# buffer.net
KiCad netlist of a schematic drawn in Altium Designer
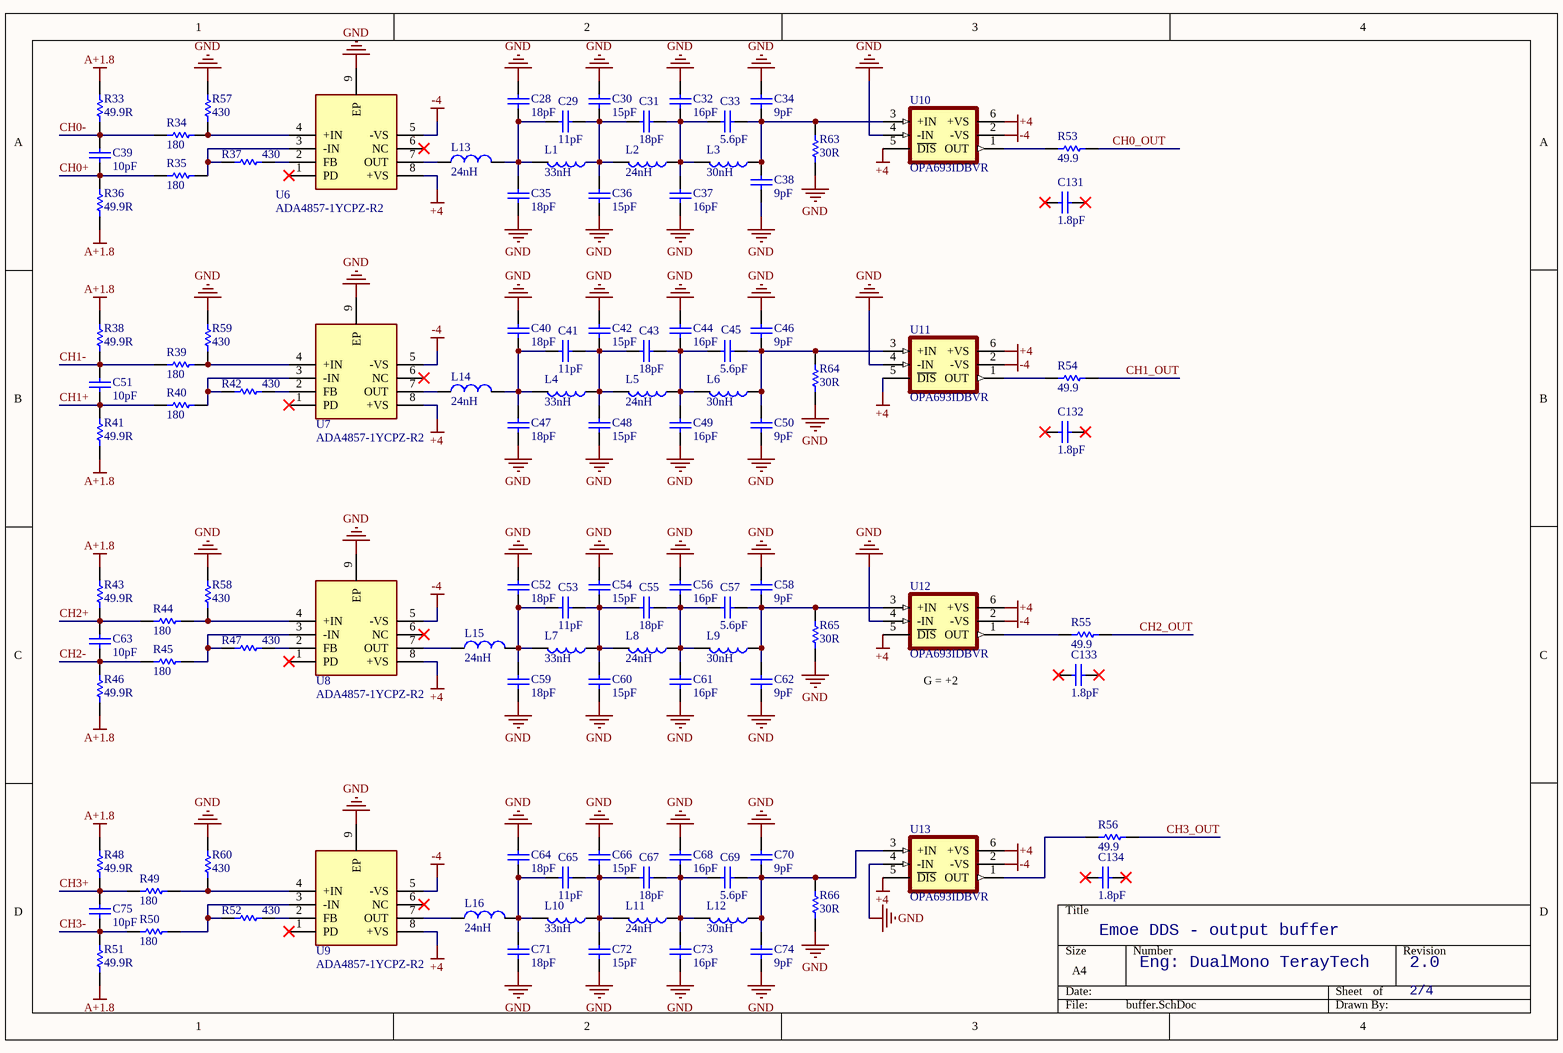
[diagram p0: buffer.SchDoc]

(export (version "E")
  (design (tool "Eeschema 10.0.6"))
  (components
    (comp (ref "C28")
      (value "18pF")
      (footprint "0402")
      (description "Capacitor")
      (fields (field (name "PUBLISHER") "Altium Limited"))
      (libsource (lib "My Footprint") (part "CAP"))
    )
    (comp (ref "C29")
      (value "11pF")
      (footprint "0402")
      (description "Capacitor")
      (fields (field (name "PUBLISHER") "Altium Limited"))
      (libsource (lib "My Footprint") (part "CAP"))
    )
    (comp (ref "C30")
      (value "15pF")
      (footprint "0402")
      (description "Capacitor")
      (fields (field (name "PUBLISHER") "Altium Limited"))
      (libsource (lib "My Footprint") (part "CAP"))
    )
    (comp (ref "C31")
      (value "18pF")
      (footprint "0402")
      (description "Capacitor")
      (fields (field (name "PUBLISHER") "Altium Limited"))
      (libsource (lib "My Footprint") (part "CAP"))
    )
    (comp (ref "C32")
      (value "16pF")
      (footprint "0402")
      (description "Capacitor")
      (fields (field (name "PUBLISHER") "Altium Limited"))
      (libsource (lib "My Footprint") (part "CAP"))
    )
    (comp (ref "C33")
      (value "5.6pF")
      (footprint "0402")
      (description "Capacitor")
      (fields (field (name "PUBLISHER") "Altium Limited"))
      (libsource (lib "My Footprint") (part "CAP"))
    )
    (comp (ref "C34")
      (value "9pF")
      (footprint "0402")
      (description "Capacitor")
      (fields (field (name "PUBLISHER") "Altium Limited"))
      (libsource (lib "My Footprint") (part "CAP"))
    )
    (comp (ref "C35")
      (value "18pF")
      (footprint "0402")
      (description "Capacitor")
      (fields (field (name "PUBLISHER") "Altium Limited"))
      (libsource (lib "My Footprint") (part "CAP"))
    )
    (comp (ref "C36")
      (value "15pF")
      (footprint "0402")
      (description "Capacitor")
      (fields (field (name "PUBLISHER") "Altium Limited"))
      (libsource (lib "My Footprint") (part "CAP"))
    )
    (comp (ref "C37")
      (value "16pF")
      (footprint "0402")
      (description "Capacitor")
      (fields (field (name "PUBLISHER") "Altium Limited"))
      (libsource (lib "My Footprint") (part "CAP"))
    )
    (comp (ref "C38")
      (value "9pF")
      (footprint "0402")
      (description "Capacitor")
      (fields (field (name "PUBLISHER") "Altium Limited"))
      (libsource (lib "My Footprint") (part "CAP"))
    )
    (comp (ref "C39")
      (value "10pF")
      (footprint "0402")
      (description "Capacitor")
      (fields (field (name "PUBLISHER") "Altium Limited"))
      (libsource (lib "My Footprint") (part "CAP"))
    )
    (comp (ref "C40")
      (value "18pF")
      (footprint "0402")
      (description "Capacitor")
      (fields (field (name "PUBLISHER") "Altium Limited"))
      (libsource (lib "My Footprint") (part "CAP"))
    )
    (comp (ref "C41")
      (value "11pF")
      (footprint "0402")
      (description "Capacitor")
      (fields (field (name "PUBLISHER") "Altium Limited"))
      (libsource (lib "My Footprint") (part "CAP"))
    )
    (comp (ref "C42")
      (value "15pF")
      (footprint "0402")
      (description "Capacitor")
      (fields (field (name "PUBLISHER") "Altium Limited"))
      (libsource (lib "My Footprint") (part "CAP"))
    )
    (comp (ref "C43")
      (value "18pF")
      (footprint "0402")
      (description "Capacitor")
      (fields (field (name "PUBLISHER") "Altium Limited"))
      (libsource (lib "My Footprint") (part "CAP"))
    )
    (comp (ref "C44")
      (value "16pF")
      (footprint "0402")
      (description "Capacitor")
      (fields (field (name "PUBLISHER") "Altium Limited"))
      (libsource (lib "My Footprint") (part "CAP"))
    )
    (comp (ref "C45")
      (value "5.6pF")
      (footprint "0402")
      (description "Capacitor")
      (fields (field (name "PUBLISHER") "Altium Limited"))
      (libsource (lib "My Footprint") (part "CAP"))
    )
    (comp (ref "C46")
      (value "9pF")
      (footprint "0402")
      (description "Capacitor")
      (fields (field (name "PUBLISHER") "Altium Limited"))
      (libsource (lib "My Footprint") (part "CAP"))
    )
    (comp (ref "C47")
      (value "18pF")
      (footprint "0402")
      (description "Capacitor")
      (fields (field (name "PUBLISHER") "Altium Limited"))
      (libsource (lib "My Footprint") (part "CAP"))
    )
    (comp (ref "C48")
      (value "15pF")
      (footprint "0402")
      (description "Capacitor")
      (fields (field (name "PUBLISHER") "Altium Limited"))
      (libsource (lib "My Footprint") (part "CAP"))
    )
    (comp (ref "C49")
      (value "16pF")
      (footprint "0402")
      (description "Capacitor")
      (fields (field (name "PUBLISHER") "Altium Limited"))
      (libsource (lib "My Footprint") (part "CAP"))
    )
    (comp (ref "C50")
      (value "9pF")
      (footprint "0402")
      (description "Capacitor")
      (fields (field (name "PUBLISHER") "Altium Limited"))
      (libsource (lib "My Footprint") (part "CAP"))
    )
    (comp (ref "C51")
      (value "10pF")
      (footprint "0402")
      (description "Capacitor")
      (fields (field (name "PUBLISHER") "Altium Limited"))
      (libsource (lib "My Footprint") (part "CAP"))
    )
    (comp (ref "C52")
      (value "18pF")
      (footprint "0402")
      (description "Capacitor")
      (fields (field (name "PUBLISHER") "Altium Limited"))
      (libsource (lib "My Footprint") (part "CAP"))
    )
    (comp (ref "C53")
      (value "11pF")
      (footprint "0402")
      (description "Capacitor")
      (fields (field (name "PUBLISHER") "Altium Limited"))
      (libsource (lib "My Footprint") (part "CAP"))
    )
    (comp (ref "C54")
      (value "15pF")
      (footprint "0402")
      (description "Capacitor")
      (fields (field (name "PUBLISHER") "Altium Limited"))
      (libsource (lib "My Footprint") (part "CAP"))
    )
    (comp (ref "C55")
      (value "18pF")
      (footprint "0402")
      (description "Capacitor")
      (fields (field (name "PUBLISHER") "Altium Limited"))
      (libsource (lib "My Footprint") (part "CAP"))
    )
    (comp (ref "C56")
      (value "16pF")
      (footprint "0402")
      (description "Capacitor")
      (fields (field (name "PUBLISHER") "Altium Limited"))
      (libsource (lib "My Footprint") (part "CAP"))
    )
    (comp (ref "C57")
      (value "5.6pF")
      (footprint "0402")
      (description "Capacitor")
      (fields (field (name "PUBLISHER") "Altium Limited"))
      (libsource (lib "My Footprint") (part "CAP"))
    )
    (comp (ref "C58")
      (value "9pF")
      (footprint "0402")
      (description "Capacitor")
      (fields (field (name "PUBLISHER") "Altium Limited"))
      (libsource (lib "My Footprint") (part "CAP"))
    )
    (comp (ref "C59")
      (value "18pF")
      (footprint "0402")
      (description "Capacitor")
      (fields (field (name "PUBLISHER") "Altium Limited"))
      (libsource (lib "My Footprint") (part "CAP"))
    )
    (comp (ref "C60")
      (value "15pF")
      (footprint "0402")
      (description "Capacitor")
      (fields (field (name "PUBLISHER") "Altium Limited"))
      (libsource (lib "My Footprint") (part "CAP"))
    )
    (comp (ref "C61")
      (value "16pF")
      (footprint "0402")
      (description "Capacitor")
      (fields (field (name "PUBLISHER") "Altium Limited"))
      (libsource (lib "My Footprint") (part "CAP"))
    )
    (comp (ref "C62")
      (value "9pF")
      (footprint "0402")
      (description "Capacitor")
      (fields (field (name "PUBLISHER") "Altium Limited"))
      (libsource (lib "My Footprint") (part "CAP"))
    )
    (comp (ref "C63")
      (value "10pF")
      (footprint "0402")
      (description "Capacitor")
      (fields (field (name "PUBLISHER") "Altium Limited"))
      (libsource (lib "My Footprint") (part "CAP"))
    )
    (comp (ref "C64")
      (value "18pF")
      (footprint "0402")
      (description "Capacitor")
      (fields (field (name "PUBLISHER") "Altium Limited"))
      (libsource (lib "My Footprint") (part "CAP"))
    )
    (comp (ref "C65")
      (value "11pF")
      (footprint "0402")
      (description "Capacitor")
      (fields (field (name "PUBLISHER") "Altium Limited"))
      (libsource (lib "My Footprint") (part "CAP"))
    )
    (comp (ref "C66")
      (value "15pF")
      (footprint "0402")
      (description "Capacitor")
      (fields (field (name "PUBLISHER") "Altium Limited"))
      (libsource (lib "My Footprint") (part "CAP"))
    )
    (comp (ref "C67")
      (value "18pF")
      (footprint "0402")
      (description "Capacitor")
      (fields (field (name "PUBLISHER") "Altium Limited"))
      (libsource (lib "My Footprint") (part "CAP"))
    )
    (comp (ref "C68")
      (value "16pF")
      (footprint "0402")
      (description "Capacitor")
      (fields (field (name "PUBLISHER") "Altium Limited"))
      (libsource (lib "My Footprint") (part "CAP"))
    )
    (comp (ref "C69")
      (value "5.6pF")
      (footprint "0402")
      (description "Capacitor")
      (fields (field (name "PUBLISHER") "Altium Limited"))
      (libsource (lib "My Footprint") (part "CAP"))
    )
    (comp (ref "C70")
      (value "9pF")
      (footprint "0402")
      (description "Capacitor")
      (fields (field (name "PUBLISHER") "Altium Limited"))
      (libsource (lib "My Footprint") (part "CAP"))
    )
    (comp (ref "C71")
      (value "18pF")
      (footprint "0402")
      (description "Capacitor")
      (fields (field (name "PUBLISHER") "Altium Limited"))
      (libsource (lib "My Footprint") (part "CAP"))
    )
    (comp (ref "C72")
      (value "15pF")
      (footprint "0402")
      (description "Capacitor")
      (fields (field (name "PUBLISHER") "Altium Limited"))
      (libsource (lib "My Footprint") (part "CAP"))
    )
    (comp (ref "C73")
      (value "16pF")
      (footprint "0402")
      (description "Capacitor")
      (fields (field (name "PUBLISHER") "Altium Limited"))
      (libsource (lib "My Footprint") (part "CAP"))
    )
    (comp (ref "C74")
      (value "9pF")
      (footprint "0402")
      (description "Capacitor")
      (fields (field (name "PUBLISHER") "Altium Limited"))
      (libsource (lib "My Footprint") (part "CAP"))
    )
    (comp (ref "C75")
      (value "10pF")
      (footprint "0402")
      (description "Capacitor")
      (fields (field (name "PUBLISHER") "Altium Limited"))
      (libsource (lib "My Footprint") (part "CAP"))
    )
    (comp (ref "C131")
      (value "1.8pF")
      (footprint "0402")
      (description "Capacitor")
      (fields (field (name "PUBLISHER") "Altium Limited"))
      (libsource (lib "My Footprint") (part "CAP"))
    )
    (comp (ref "C132")
      (value "1.8pF")
      (footprint "0402")
      (description "Capacitor")
      (fields (field (name "PUBLISHER") "Altium Limited"))
      (libsource (lib "My Footprint") (part "CAP"))
    )
    (comp (ref "C133")
      (value "1.8pF")
      (footprint "0402")
      (description "Capacitor")
      (fields (field (name "PUBLISHER") "Altium Limited"))
      (libsource (lib "My Footprint") (part "CAP"))
    )
    (comp (ref "C134")
      (value "1.8pF")
      (footprint "0402")
      (description "Capacitor")
      (fields (field (name "PUBLISHER") "Altium Limited"))
      (libsource (lib "My Footprint") (part "CAP"))
    )
    (comp (ref "L1") (value "33nH") (footprint "0402") (libsource (lib "My Footprint") (part "FB")))
    (comp (ref "L2") (value "24nH") (footprint "0402") (libsource (lib "My Footprint") (part "FB")))
    (comp (ref "L3") (value "30nH") (footprint "0402") (libsource (lib "My Footprint") (part "FB")))
    (comp (ref "L4") (value "33nH") (footprint "0402") (libsource (lib "My Footprint") (part "FB")))
    (comp (ref "L5") (value "24nH") (footprint "0402") (libsource (lib "My Footprint") (part "FB")))
    (comp (ref "L6") (value "30nH") (footprint "0402") (libsource (lib "My Footprint") (part "FB")))
    (comp (ref "L7") (value "33nH") (footprint "0402") (libsource (lib "My Footprint") (part "FB")))
    (comp (ref "L8") (value "24nH") (footprint "0402") (libsource (lib "My Footprint") (part "FB")))
    (comp (ref "L9") (value "30nH") (footprint "0402") (libsource (lib "My Footprint") (part "FB")))
    (comp (ref "L10") (value "33nH") (footprint "0402") (libsource (lib "My Footprint") (part "FB")))
    (comp (ref "L11") (value "24nH") (footprint "0402") (libsource (lib "My Footprint") (part "FB")))
    (comp (ref "L12") (value "30nH") (footprint "0402") (libsource (lib "My Footprint") (part "FB")))
    (comp (ref "L13") (value "24nH") (footprint "0402L") (libsource (lib "My Footprint") (part "Inductor")))
    (comp (ref "L14") (value "24nH") (footprint "0402L") (libsource (lib "My Footprint") (part "Inductor")))
    (comp (ref "L15") (value "24nH") (footprint "0402L") (libsource (lib "My Footprint") (part "Inductor")))
    (comp (ref "L16") (value "24nH") (footprint "0402L") (libsource (lib "My Footprint") (part "Inductor")))
    (comp (ref "R33")
      (value "49.9R")
      (footprint "0402")
      (description "Resistor")
      (fields (field (name "PUBLISHER") "Altium Limited"))
      (libsource (lib "My Footprint") (part "RES"))
    )
    (comp (ref "R34")
      (value "180")
      (footprint "0402")
      (description "Resistor")
      (fields (field (name "PUBLISHER") "Altium Limited"))
      (libsource (lib "My Footprint") (part "RES"))
    )
    (comp (ref "R35")
      (value "180")
      (footprint "0402")
      (description "Resistor")
      (fields (field (name "PUBLISHER") "Altium Limited"))
      (libsource (lib "My Footprint") (part "RES"))
    )
    (comp (ref "R36")
      (value "49.9R")
      (footprint "0402")
      (description "Resistor")
      (fields (field (name "PUBLISHER") "Altium Limited"))
      (libsource (lib "My Footprint") (part "RES"))
    )
    (comp (ref "R37")
      (value "430")
      (footprint "0402")
      (description "Resistor")
      (fields (field (name "PUBLISHER") "Altium Limited"))
      (libsource (lib "My Footprint") (part "RES"))
    )
    (comp (ref "R38")
      (value "49.9R")
      (footprint "0402")
      (description "Resistor")
      (fields (field (name "PUBLISHER") "Altium Limited"))
      (libsource (lib "My Footprint") (part "RES"))
    )
    (comp (ref "R39")
      (value "180")
      (footprint "0402")
      (description "Resistor")
      (fields (field (name "PUBLISHER") "Altium Limited"))
      (libsource (lib "My Footprint") (part "RES"))
    )
    (comp (ref "R40")
      (value "180")
      (footprint "0402")
      (description "Resistor")
      (fields (field (name "PUBLISHER") "Altium Limited"))
      (libsource (lib "My Footprint") (part "RES"))
    )
    (comp (ref "R41")
      (value "49.9R")
      (footprint "0402")
      (description "Resistor")
      (fields (field (name "PUBLISHER") "Altium Limited"))
      (libsource (lib "My Footprint") (part "RES"))
    )
    (comp (ref "R42")
      (value "430")
      (footprint "0402")
      (description "Resistor")
      (fields (field (name "PUBLISHER") "Altium Limited"))
      (libsource (lib "My Footprint") (part "RES"))
    )
    (comp (ref "R43")
      (value "49.9R")
      (footprint "0402")
      (description "Resistor")
      (fields (field (name "PUBLISHER") "Altium Limited"))
      (libsource (lib "My Footprint") (part "RES"))
    )
    (comp (ref "R44")
      (value "180")
      (footprint "0402")
      (description "Resistor")
      (fields (field (name "PUBLISHER") "Altium Limited"))
      (libsource (lib "My Footprint") (part "RES"))
    )
    (comp (ref "R45")
      (value "180")
      (footprint "0402")
      (description "Resistor")
      (fields (field (name "PUBLISHER") "Altium Limited"))
      (libsource (lib "My Footprint") (part "RES"))
    )
    (comp (ref "R46")
      (value "49.9R")
      (footprint "0402")
      (description "Resistor")
      (fields (field (name "PUBLISHER") "Altium Limited"))
      (libsource (lib "My Footprint") (part "RES"))
    )
    (comp (ref "R47")
      (value "430")
      (footprint "0402")
      (description "Resistor")
      (fields (field (name "PUBLISHER") "Altium Limited"))
      (libsource (lib "My Footprint") (part "RES"))
    )
    (comp (ref "R48")
      (value "49.9R")
      (footprint "0402")
      (description "Resistor")
      (fields (field (name "PUBLISHER") "Altium Limited"))
      (libsource (lib "My Footprint") (part "RES"))
    )
    (comp (ref "R49")
      (value "180")
      (footprint "0402")
      (description "Resistor")
      (fields (field (name "PUBLISHER") "Altium Limited"))
      (libsource (lib "My Footprint") (part "RES"))
    )
    (comp (ref "R50")
      (value "180")
      (footprint "0402")
      (description "Resistor")
      (fields (field (name "PUBLISHER") "Altium Limited"))
      (libsource (lib "My Footprint") (part "RES"))
    )
    (comp (ref "R51")
      (value "49.9R")
      (footprint "0402")
      (description "Resistor")
      (fields (field (name "PUBLISHER") "Altium Limited"))
      (libsource (lib "My Footprint") (part "RES"))
    )
    (comp (ref "R52")
      (value "430")
      (footprint "0402")
      (description "Resistor")
      (fields (field (name "PUBLISHER") "Altium Limited"))
      (libsource (lib "My Footprint") (part "RES"))
    )
    (comp (ref "R53")
      (value "49.9")
      (footprint "0603")
      (description "Resistor")
      (fields (field (name "PUBLISHER") "Altium Limited"))
      (libsource (lib "My Footprint") (part "RES"))
    )
    (comp (ref "R54")
      (value "49.9")
      (footprint "0603")
      (description "Resistor")
      (fields (field (name "PUBLISHER") "Altium Limited"))
      (libsource (lib "My Footprint") (part "RES"))
    )
    (comp (ref "R55")
      (value "49.9")
      (footprint "0603")
      (description "Resistor")
      (fields (field (name "PUBLISHER") "Altium Limited"))
      (libsource (lib "My Footprint") (part "RES"))
    )
    (comp (ref "R56")
      (value "49.9")
      (footprint "0603")
      (description "Resistor")
      (fields (field (name "PUBLISHER") "Altium Limited"))
      (libsource (lib "My Footprint") (part "RES"))
    )
    (comp (ref "R57")
      (value "430")
      (footprint "0402")
      (description "Resistor")
      (fields (field (name "PUBLISHER") "Altium Limited"))
      (libsource (lib "My Footprint") (part "RES"))
    )
    (comp (ref "R58")
      (value "430")
      (footprint "0402")
      (description "Resistor")
      (fields (field (name "PUBLISHER") "Altium Limited"))
      (libsource (lib "My Footprint") (part "RES"))
    )
    (comp (ref "R59")
      (value "430")
      (footprint "0402")
      (description "Resistor")
      (fields (field (name "PUBLISHER") "Altium Limited"))
      (libsource (lib "My Footprint") (part "RES"))
    )
    (comp (ref "R60")
      (value "430")
      (footprint "0402")
      (description "Resistor")
      (fields (field (name "PUBLISHER") "Altium Limited"))
      (libsource (lib "My Footprint") (part "RES"))
    )
    (comp (ref "R63")
      (value "30R")
      (footprint "0402L")
      (description "Resistor")
      (fields (field (name "PUBLISHER") "Altium Limited"))
      (libsource (lib "My Footprint") (part "RES"))
    )
    (comp (ref "R64")
      (value "30R")
      (footprint "0402L")
      (description "Resistor")
      (fields (field (name "PUBLISHER") "Altium Limited"))
      (libsource (lib "My Footprint") (part "RES"))
    )
    (comp (ref "R65")
      (value "30R")
      (footprint "0402L")
      (description "Resistor")
      (fields (field (name "PUBLISHER") "Altium Limited"))
      (libsource (lib "My Footprint") (part "RES"))
    )
    (comp (ref "R66")
      (value "30R")
      (footprint "0402L")
      (description "Resistor")
      (fields (field (name "PUBLISHER") "Altium Limited"))
      (libsource (lib "My Footprint") (part "RES"))
    )
    (comp (ref "U6")
      (value "ADA4857-1YCPZ-R2")
      (footprint "SamacSys:SON50P300X300X85-9N-D")
      (description "Integrated Circuit")
      (fields (field (name "MOUSER PART NUMBER") "584-ADA4857-1YCPZ-R2"))
      (libsource (lib "SamacSys") (part "ADA4857-1YCPZ-R2"))
    )
    (comp (ref "U7")
      (value "ADA4857-1YCPZ-R2")
      (footprint "SamacSys:SON50P300X300X85-9N-D")
      (description "Integrated Circuit")
      (fields (field (name "MOUSER PART NUMBER") "584-ADA4857-1YCPZ-R2"))
      (libsource (lib "SamacSys") (part "ADA4857-1YCPZ-R2"))
    )
    (comp (ref "U8")
      (value "ADA4857-1YCPZ-R2")
      (footprint "SamacSys:SON50P300X300X85-9N-D")
      (description "Integrated Circuit")
      (fields (field (name "MOUSER PART NUMBER") "584-ADA4857-1YCPZ-R2"))
      (libsource (lib "SamacSys") (part "ADA4857-1YCPZ-R2"))
    )
    (comp (ref "U9")
      (value "ADA4857-1YCPZ-R2")
      (footprint "SamacSys:SON50P300X300X85-9N-D")
      (description "Integrated Circuit")
      (fields (field (name "MOUSER PART NUMBER") "584-ADA4857-1YCPZ-R2"))
      (libsource (lib "SamacSys") (part "ADA4857-1YCPZ-R2"))
    )
    (comp (ref "U10")
      (value "OPA693IDBVR")
      (footprint "SOT95P280X145-6N")
      (description "Ultra-Wideband, Fixed Gain Video Buffer Amplifier with Disable")
      (fields (field (name "MF") "Texas Instruments"))
      (libsource (lib "OPA693") (part "OPA693IDBVR"))
    )
    (comp (ref "U11")
      (value "OPA693IDBVR")
      (footprint "SOT95P280X145-6N")
      (description "Ultra-Wideband, Fixed Gain Video Buffer Amplifier with Disable")
      (fields (field (name "MF") "Texas Instruments"))
      (libsource (lib "OPA693") (part "OPA693IDBVR"))
    )
    (comp (ref "U12")
      (value "OPA693IDBVR")
      (footprint "SOT95P280X145-6N")
      (description "Ultra-Wideband, Fixed Gain Video Buffer Amplifier with Disable")
      (fields (field (name "MF") "Texas Instruments"))
      (libsource (lib "OPA693") (part "OPA693IDBVR"))
    )
    (comp (ref "U13")
      (value "OPA693IDBVR")
      (footprint "SOT95P280X145-6N")
      (description "Ultra-Wideband, Fixed Gain Video Buffer Amplifier with Disable")
      (fields (field (name "MF") "Texas Instruments"))
      (libsource (lib "OPA693") (part "OPA693IDBVR"))
    )
  )
  (nets
    (net (code "1") (name "+4") (class "Default")
      (node (ref "U10") (pin "5") (pinfunction "~{DIS}_5") (pintype "passive"))
      (node (ref "U10") (pin "6") (pinfunction "+VS_6") (pintype "power_in"))
      (node (ref "U11") (pin "5") (pinfunction "~{DIS}_5") (pintype "passive"))
      (node (ref "U11") (pin "6") (pinfunction "+VS_6") (pintype "power_in"))
      (node (ref "U12") (pin "5") (pinfunction "~{DIS}_5") (pintype "passive"))
      (node (ref "U12") (pin "6") (pinfunction "+VS_6") (pintype "power_in"))
      (node (ref "U13") (pin "5") (pinfunction "~{DIS}_5") (pintype "passive"))
      (node (ref "U13") (pin "6") (pinfunction "+VS_6") (pintype "power_in"))
      (node (ref "U6") (pin "8") (pinfunction "+VS_8") (pintype "passive"))
      (node (ref "U7") (pin "8") (pinfunction "+VS_8") (pintype "passive"))
      (node (ref "U8") (pin "8") (pinfunction "+VS_8") (pintype "passive"))
      (node (ref "U9") (pin "8") (pinfunction "+VS_8") (pintype "passive"))
    )
    (net (code "2") (name "-4") (class "Default")
      (node (ref "U10") (pin "2") (pinfunction "-VS_2") (pintype "power_in"))
      (node (ref "U11") (pin "2") (pinfunction "-VS_2") (pintype "power_in"))
      (node (ref "U12") (pin "2") (pinfunction "-VS_2") (pintype "power_in"))
      (node (ref "U13") (pin "2") (pinfunction "-VS_2") (pintype "power_in"))
      (node (ref "U6") (pin "5") (pinfunction "-VS_5") (pintype "passive"))
      (node (ref "U7") (pin "5") (pinfunction "-VS_5") (pintype "passive"))
      (node (ref "U8") (pin "5") (pinfunction "-VS_5") (pintype "passive"))
      (node (ref "U9") (pin "5") (pinfunction "-VS_5") (pintype "passive"))
    )
    (net (code "3") (name "/CH0+") (class "Default")
      (node (ref "C39") (pin "1") (pinfunction "1_1") (pintype "passive"))
      (node (ref "R35") (pin "1") (pinfunction "1_1") (pintype "passive"))
      (node (ref "R36") (pin "1") (pinfunction "1_1") (pintype "passive"))
    )
    (net (code "4") (name "/CH0-") (class "Default")
      (node (ref "C39") (pin "2") (pinfunction "2_2") (pintype "passive"))
      (node (ref "R33") (pin "2") (pinfunction "2_2") (pintype "passive"))
      (node (ref "R34") (pin "1") (pinfunction "1_1") (pintype "passive"))
    )
    (net (code "5") (name "/CH0_OUT") (class "Default")
      (node (ref "R53") (pin "2") (pinfunction "2_2") (pintype "passive"))
    )
    (net (code "6") (name "/CH1+") (class "Default")
      (node (ref "C51") (pin "1") (pinfunction "1_1") (pintype "passive"))
      (node (ref "R40") (pin "1") (pinfunction "1_1") (pintype "passive"))
      (node (ref "R41") (pin "1") (pinfunction "1_1") (pintype "passive"))
    )
    (net (code "7") (name "/CH1-") (class "Default")
      (node (ref "C51") (pin "2") (pinfunction "2_2") (pintype "passive"))
      (node (ref "R38") (pin "2") (pinfunction "2_2") (pintype "passive"))
      (node (ref "R39") (pin "1") (pinfunction "1_1") (pintype "passive"))
    )
    (net (code "8") (name "/CH1_OUT") (class "Default")
      (node (ref "R54") (pin "2") (pinfunction "2_2") (pintype "passive"))
    )
    (net (code "9") (name "/CH2+") (class "Default")
      (node (ref "C63") (pin "2") (pinfunction "2_2") (pintype "passive"))
      (node (ref "R43") (pin "2") (pinfunction "2_2") (pintype "passive"))
      (node (ref "R44") (pin "1") (pinfunction "1_1") (pintype "passive"))
    )
    (net (code "10") (name "/CH2-") (class "Default")
      (node (ref "C63") (pin "1") (pinfunction "1_1") (pintype "passive"))
      (node (ref "R45") (pin "1") (pinfunction "1_1") (pintype "passive"))
      (node (ref "R46") (pin "1") (pinfunction "1_1") (pintype "passive"))
    )
    (net (code "11") (name "/CH2_OUT") (class "Default")
      (node (ref "R55") (pin "2") (pinfunction "2_2") (pintype "passive"))
    )
    (net (code "12") (name "/CH3+") (class "Default")
      (node (ref "C75") (pin "2") (pinfunction "2_2") (pintype "passive"))
      (node (ref "R48") (pin "2") (pinfunction "2_2") (pintype "passive"))
      (node (ref "R49") (pin "1") (pinfunction "1_1") (pintype "passive"))
    )
    (net (code "13") (name "/CH3-") (class "Default")
      (node (ref "C75") (pin "1") (pinfunction "1_1") (pintype "passive"))
      (node (ref "R50") (pin "1") (pinfunction "1_1") (pintype "passive"))
      (node (ref "R51") (pin "1") (pinfunction "1_1") (pintype "passive"))
    )
    (net (code "14") (name "/CH3_OUT") (class "Default")
      (node (ref "R56") (pin "2") (pinfunction "2_2") (pintype "passive"))
    )
    (net (code "15") (name "A+1.8") (class "Default")
      (node (ref "R33") (pin "1") (pinfunction "1_1") (pintype "passive"))
      (node (ref "R36") (pin "2") (pinfunction "2_2") (pintype "passive"))
      (node (ref "R38") (pin "1") (pinfunction "1_1") (pintype "passive"))
      (node (ref "R41") (pin "2") (pinfunction "2_2") (pintype "passive"))
      (node (ref "R43") (pin "1") (pinfunction "1_1") (pintype "passive"))
      (node (ref "R46") (pin "2") (pinfunction "2_2") (pintype "passive"))
      (node (ref "R48") (pin "1") (pinfunction "1_1") (pintype "passive"))
      (node (ref "R51") (pin "2") (pinfunction "2_2") (pintype "passive"))
    )
    (net (code "16") (name "GND") (class "Default")
      (node (ref "C28") (pin "1") (pinfunction "1_1") (pintype "passive"))
      (node (ref "C30") (pin "1") (pinfunction "1_1") (pintype "passive"))
      (node (ref "C32") (pin "1") (pinfunction "1_1") (pintype "passive"))
      (node (ref "C34") (pin "2") (pinfunction "2_2") (pintype "passive"))
      (node (ref "C35") (pin "2") (pinfunction "2_2") (pintype "passive"))
      (node (ref "C36") (pin "2") (pinfunction "2_2") (pintype "passive"))
      (node (ref "C37") (pin "2") (pinfunction "2_2") (pintype "passive"))
      (node (ref "C38") (pin "1") (pinfunction "1_1") (pintype "passive"))
      (node (ref "C40") (pin "1") (pinfunction "1_1") (pintype "passive"))
      (node (ref "C42") (pin "1") (pinfunction "1_1") (pintype "passive"))
      (node (ref "C44") (pin "1") (pinfunction "1_1") (pintype "passive"))
      (node (ref "C46") (pin "2") (pinfunction "2_2") (pintype "passive"))
      (node (ref "C47") (pin "2") (pinfunction "2_2") (pintype "passive"))
      (node (ref "C48") (pin "2") (pinfunction "2_2") (pintype "passive"))
      (node (ref "C49") (pin "2") (pinfunction "2_2") (pintype "passive"))
      (node (ref "C50") (pin "1") (pinfunction "1_1") (pintype "passive"))
      (node (ref "C52") (pin "1") (pinfunction "1_1") (pintype "passive"))
      (node (ref "C54") (pin "1") (pinfunction "1_1") (pintype "passive"))
      (node (ref "C56") (pin "1") (pinfunction "1_1") (pintype "passive"))
      (node (ref "C58") (pin "2") (pinfunction "2_2") (pintype "passive"))
      (node (ref "C59") (pin "2") (pinfunction "2_2") (pintype "passive"))
      (node (ref "C60") (pin "2") (pinfunction "2_2") (pintype "passive"))
      (node (ref "C61") (pin "2") (pinfunction "2_2") (pintype "passive"))
      (node (ref "C62") (pin "1") (pinfunction "1_1") (pintype "passive"))
      (node (ref "C64") (pin "1") (pinfunction "1_1") (pintype "passive"))
      (node (ref "C66") (pin "1") (pinfunction "1_1") (pintype "passive"))
      (node (ref "C68") (pin "1") (pinfunction "1_1") (pintype "passive"))
      (node (ref "C70") (pin "2") (pinfunction "2_2") (pintype "passive"))
      (node (ref "C71") (pin "2") (pinfunction "2_2") (pintype "passive"))
      (node (ref "C72") (pin "2") (pinfunction "2_2") (pintype "passive"))
      (node (ref "C73") (pin "2") (pinfunction "2_2") (pintype "passive"))
      (node (ref "C74") (pin "1") (pinfunction "1_1") (pintype "passive"))
      (node (ref "R57") (pin "2") (pinfunction "2_2") (pintype "passive"))
      (node (ref "R58") (pin "2") (pinfunction "2_2") (pintype "passive"))
      (node (ref "R59") (pin "2") (pinfunction "2_2") (pintype "passive"))
      (node (ref "R60") (pin "2") (pinfunction "2_2") (pintype "passive"))
      (node (ref "R63") (pin "1") (pinfunction "1_1") (pintype "passive"))
      (node (ref "R64") (pin "1") (pinfunction "1_1") (pintype "passive"))
      (node (ref "R65") (pin "1") (pinfunction "1_1") (pintype "passive"))
      (node (ref "R66") (pin "1") (pinfunction "1_1") (pintype "passive"))
      (node (ref "U10") (pin "4") (pinfunction "-IN_4") (pintype "input"))
      (node (ref "U11") (pin "4") (pinfunction "-IN_4") (pintype "input"))
      (node (ref "U12") (pin "4") (pinfunction "-IN_4") (pintype "input"))
      (node (ref "U13") (pin "4") (pinfunction "-IN_4") (pintype "input"))
      (node (ref "U6") (pin "9") (pinfunction "EP_9") (pintype "passive"))
      (node (ref "U7") (pin "9") (pinfunction "EP_9") (pintype "passive"))
      (node (ref "U8") (pin "9") (pinfunction "EP_9") (pintype "passive"))
      (node (ref "U9") (pin "9") (pinfunction "EP_9") (pintype "passive"))
    )
    (net (code "17") (name "Net-(C28-Pad2)") (class "Default")
      (node (ref "C28") (pin "2") (pinfunction "2_2") (pintype "passive"))
      (node (ref "C29") (pin "1") (pinfunction "1_1") (pintype "passive"))
      (node (ref "C35") (pin "1") (pinfunction "1_1") (pintype "passive"))
      (node (ref "L1") (pin "2") (pinfunction "2_2") (pintype "passive"))
      (node (ref "L13") (pin "2") (pinfunction "2_2") (pintype "passive"))
    )
    (net (code "18") (name "Net-(C29-Pad2)") (class "Default")
      (node (ref "C29") (pin "2") (pinfunction "2_2") (pintype "passive"))
      (node (ref "C30") (pin "2") (pinfunction "2_2") (pintype "passive"))
      (node (ref "C31") (pin "1") (pinfunction "1_1") (pintype "passive"))
      (node (ref "C36") (pin "1") (pinfunction "1_1") (pintype "passive"))
      (node (ref "L1") (pin "1") (pinfunction "1_1") (pintype "passive"))
      (node (ref "L2") (pin "2") (pinfunction "2_2") (pintype "passive"))
    )
    (net (code "19") (name "Net-(C31-Pad2)") (class "Default")
      (node (ref "C31") (pin "2") (pinfunction "2_2") (pintype "passive"))
      (node (ref "C32") (pin "2") (pinfunction "2_2") (pintype "passive"))
      (node (ref "C33") (pin "1") (pinfunction "1_1") (pintype "passive"))
      (node (ref "C37") (pin "1") (pinfunction "1_1") (pintype "passive"))
      (node (ref "L2") (pin "1") (pinfunction "1_1") (pintype "passive"))
      (node (ref "L3") (pin "2") (pinfunction "2_2") (pintype "passive"))
    )
    (net (code "20") (name "Net-(C40-Pad2)") (class "Default")
      (node (ref "C40") (pin "2") (pinfunction "2_2") (pintype "passive"))
      (node (ref "C41") (pin "1") (pinfunction "1_1") (pintype "passive"))
      (node (ref "C47") (pin "1") (pinfunction "1_1") (pintype "passive"))
      (node (ref "L14") (pin "2") (pinfunction "2_2") (pintype "passive"))
      (node (ref "L4") (pin "2") (pinfunction "2_2") (pintype "passive"))
    )
    (net (code "21") (name "Net-(C41-Pad2)") (class "Default")
      (node (ref "C41") (pin "2") (pinfunction "2_2") (pintype "passive"))
      (node (ref "C42") (pin "2") (pinfunction "2_2") (pintype "passive"))
      (node (ref "C43") (pin "1") (pinfunction "1_1") (pintype "passive"))
      (node (ref "C48") (pin "1") (pinfunction "1_1") (pintype "passive"))
      (node (ref "L4") (pin "1") (pinfunction "1_1") (pintype "passive"))
      (node (ref "L5") (pin "2") (pinfunction "2_2") (pintype "passive"))
    )
    (net (code "22") (name "Net-(C43-Pad2)") (class "Default")
      (node (ref "C43") (pin "2") (pinfunction "2_2") (pintype "passive"))
      (node (ref "C44") (pin "2") (pinfunction "2_2") (pintype "passive"))
      (node (ref "C45") (pin "1") (pinfunction "1_1") (pintype "passive"))
      (node (ref "C49") (pin "1") (pinfunction "1_1") (pintype "passive"))
      (node (ref "L5") (pin "1") (pinfunction "1_1") (pintype "passive"))
      (node (ref "L6") (pin "2") (pinfunction "2_2") (pintype "passive"))
    )
    (net (code "23") (name "Net-(C52-Pad2)") (class "Default")
      (node (ref "C52") (pin "2") (pinfunction "2_2") (pintype "passive"))
      (node (ref "C53") (pin "1") (pinfunction "1_1") (pintype "passive"))
      (node (ref "C59") (pin "1") (pinfunction "1_1") (pintype "passive"))
      (node (ref "L15") (pin "2") (pinfunction "2_2") (pintype "passive"))
      (node (ref "L7") (pin "2") (pinfunction "2_2") (pintype "passive"))
    )
    (net (code "24") (name "Net-(C53-Pad2)") (class "Default")
      (node (ref "C53") (pin "2") (pinfunction "2_2") (pintype "passive"))
      (node (ref "C54") (pin "2") (pinfunction "2_2") (pintype "passive"))
      (node (ref "C55") (pin "1") (pinfunction "1_1") (pintype "passive"))
      (node (ref "C60") (pin "1") (pinfunction "1_1") (pintype "passive"))
      (node (ref "L7") (pin "1") (pinfunction "1_1") (pintype "passive"))
      (node (ref "L8") (pin "2") (pinfunction "2_2") (pintype "passive"))
    )
    (net (code "25") (name "Net-(C55-Pad2)") (class "Default")
      (node (ref "C55") (pin "2") (pinfunction "2_2") (pintype "passive"))
      (node (ref "C56") (pin "2") (pinfunction "2_2") (pintype "passive"))
      (node (ref "C57") (pin "1") (pinfunction "1_1") (pintype "passive"))
      (node (ref "C61") (pin "1") (pinfunction "1_1") (pintype "passive"))
      (node (ref "L8") (pin "1") (pinfunction "1_1") (pintype "passive"))
      (node (ref "L9") (pin "2") (pinfunction "2_2") (pintype "passive"))
    )
    (net (code "26") (name "Net-(C64-Pad2)") (class "Default")
      (node (ref "C64") (pin "2") (pinfunction "2_2") (pintype "passive"))
      (node (ref "C65") (pin "1") (pinfunction "1_1") (pintype "passive"))
      (node (ref "C71") (pin "1") (pinfunction "1_1") (pintype "passive"))
      (node (ref "L10") (pin "2") (pinfunction "2_2") (pintype "passive"))
      (node (ref "L16") (pin "2") (pinfunction "2_2") (pintype "passive"))
    )
    (net (code "27") (name "Net-(C65-Pad2)") (class "Default")
      (node (ref "C65") (pin "2") (pinfunction "2_2") (pintype "passive"))
      (node (ref "C66") (pin "2") (pinfunction "2_2") (pintype "passive"))
      (node (ref "C67") (pin "1") (pinfunction "1_1") (pintype "passive"))
      (node (ref "C72") (pin "1") (pinfunction "1_1") (pintype "passive"))
      (node (ref "L10") (pin "1") (pinfunction "1_1") (pintype "passive"))
      (node (ref "L11") (pin "2") (pinfunction "2_2") (pintype "passive"))
    )
    (net (code "28") (name "Net-(C67-Pad2)") (class "Default")
      (node (ref "C67") (pin "2") (pinfunction "2_2") (pintype "passive"))
      (node (ref "C68") (pin "2") (pinfunction "2_2") (pintype "passive"))
      (node (ref "C69") (pin "1") (pinfunction "1_1") (pintype "passive"))
      (node (ref "C73") (pin "1") (pinfunction "1_1") (pintype "passive"))
      (node (ref "L11") (pin "1") (pinfunction "1_1") (pintype "passive"))
      (node (ref "L12") (pin "2") (pinfunction "2_2") (pintype "passive"))
    )
    (net (code "29") (name "Net-(U6-+IN)") (class "Default")
      (node (ref "R34") (pin "2") (pinfunction "2_2") (pintype "passive"))
      (node (ref "R57") (pin "1") (pinfunction "1_1") (pintype "passive"))
      (node (ref "U6") (pin "4") (pinfunction "+IN_4") (pintype "passive"))
    )
    (net (code "30") (name "Net-(U6--IN)") (class "Default")
      (node (ref "R35") (pin "2") (pinfunction "2_2") (pintype "passive"))
      (node (ref "R37") (pin "1") (pinfunction "1_1") (pintype "passive"))
      (node (ref "U6") (pin "3") (pinfunction "-IN_3") (pintype "passive"))
    )
    (net (code "31") (name "Net-(U6-FB)") (class "Default")
      (node (ref "R37") (pin "2") (pinfunction "2_2") (pintype "passive"))
      (node (ref "U6") (pin "2") (pinfunction "FB_2") (pintype "passive"))
    )
    (net (code "32") (name "Net-(U6-OUT)") (class "Default")
      (node (ref "L13") (pin "1") (pinfunction "1_1") (pintype "passive"))
      (node (ref "U6") (pin "7") (pinfunction "OUT_7") (pintype "passive"))
    )
    (net (code "33") (name "Net-(U7-+IN)") (class "Default")
      (node (ref "R39") (pin "2") (pinfunction "2_2") (pintype "passive"))
      (node (ref "R59") (pin "1") (pinfunction "1_1") (pintype "passive"))
      (node (ref "U7") (pin "4") (pinfunction "+IN_4") (pintype "passive"))
    )
    (net (code "34") (name "Net-(U7--IN)") (class "Default")
      (node (ref "R40") (pin "2") (pinfunction "2_2") (pintype "passive"))
      (node (ref "R42") (pin "1") (pinfunction "1_1") (pintype "passive"))
      (node (ref "U7") (pin "3") (pinfunction "-IN_3") (pintype "passive"))
    )
    (net (code "35") (name "Net-(U7-FB)") (class "Default")
      (node (ref "R42") (pin "2") (pinfunction "2_2") (pintype "passive"))
      (node (ref "U7") (pin "2") (pinfunction "FB_2") (pintype "passive"))
    )
    (net (code "36") (name "Net-(U7-OUT)") (class "Default")
      (node (ref "L14") (pin "1") (pinfunction "1_1") (pintype "passive"))
      (node (ref "U7") (pin "7") (pinfunction "OUT_7") (pintype "passive"))
    )
    (net (code "37") (name "Net-(U8-+IN)") (class "Default")
      (node (ref "R44") (pin "2") (pinfunction "2_2") (pintype "passive"))
      (node (ref "R58") (pin "1") (pinfunction "1_1") (pintype "passive"))
      (node (ref "U8") (pin "4") (pinfunction "+IN_4") (pintype "passive"))
    )
    (net (code "38") (name "Net-(U8--IN)") (class "Default")
      (node (ref "R45") (pin "2") (pinfunction "2_2") (pintype "passive"))
      (node (ref "R47") (pin "1") (pinfunction "1_1") (pintype "passive"))
      (node (ref "U8") (pin "3") (pinfunction "-IN_3") (pintype "passive"))
    )
    (net (code "39") (name "Net-(U8-FB)") (class "Default")
      (node (ref "R47") (pin "2") (pinfunction "2_2") (pintype "passive"))
      (node (ref "U8") (pin "2") (pinfunction "FB_2") (pintype "passive"))
    )
    (net (code "40") (name "Net-(U8-OUT)") (class "Default")
      (node (ref "L15") (pin "1") (pinfunction "1_1") (pintype "passive"))
      (node (ref "U8") (pin "7") (pinfunction "OUT_7") (pintype "passive"))
    )
    (net (code "41") (name "Net-(U9-+IN)") (class "Default")
      (node (ref "R49") (pin "2") (pinfunction "2_2") (pintype "passive"))
      (node (ref "R60") (pin "1") (pinfunction "1_1") (pintype "passive"))
      (node (ref "U9") (pin "4") (pinfunction "+IN_4") (pintype "passive"))
    )
    (net (code "42") (name "Net-(U9--IN)") (class "Default")
      (node (ref "R50") (pin "2") (pinfunction "2_2") (pintype "passive"))
      (node (ref "R52") (pin "1") (pinfunction "1_1") (pintype "passive"))
      (node (ref "U9") (pin "3") (pinfunction "-IN_3") (pintype "passive"))
    )
    (net (code "43") (name "Net-(U9-FB)") (class "Default")
      (node (ref "R52") (pin "2") (pinfunction "2_2") (pintype "passive"))
      (node (ref "U9") (pin "2") (pinfunction "FB_2") (pintype "passive"))
    )
    (net (code "44") (name "Net-(U9-OUT)") (class "Default")
      (node (ref "L16") (pin "1") (pinfunction "1_1") (pintype "passive"))
      (node (ref "U9") (pin "7") (pinfunction "OUT_7") (pintype "passive"))
    )
    (net (code "45") (name "Net-(U10-+IN)") (class "Default")
      (node (ref "C33") (pin "2") (pinfunction "2_2") (pintype "passive"))
      (node (ref "C34") (pin "1") (pinfunction "1_1") (pintype "passive"))
      (node (ref "C38") (pin "2") (pinfunction "2_2") (pintype "passive"))
      (node (ref "L3") (pin "1") (pinfunction "1_1") (pintype "passive"))
      (node (ref "R63") (pin "2") (pinfunction "2_2") (pintype "passive"))
      (node (ref "U10") (pin "3") (pinfunction "+IN_3") (pintype "input"))
    )
    (net (code "46") (name "Net-(U10-OUT)") (class "Default")
      (node (ref "R53") (pin "1") (pinfunction "1_1") (pintype "passive"))
      (node (ref "U10") (pin "1") (pinfunction "OUT_1") (pintype "output"))
    )
    (net (code "47") (name "Net-(U11-+IN)") (class "Default")
      (node (ref "C45") (pin "2") (pinfunction "2_2") (pintype "passive"))
      (node (ref "C46") (pin "1") (pinfunction "1_1") (pintype "passive"))
      (node (ref "C50") (pin "2") (pinfunction "2_2") (pintype "passive"))
      (node (ref "L6") (pin "1") (pinfunction "1_1") (pintype "passive"))
      (node (ref "R64") (pin "2") (pinfunction "2_2") (pintype "passive"))
      (node (ref "U11") (pin "3") (pinfunction "+IN_3") (pintype "input"))
    )
    (net (code "48") (name "Net-(U11-OUT)") (class "Default")
      (node (ref "R54") (pin "1") (pinfunction "1_1") (pintype "passive"))
      (node (ref "U11") (pin "1") (pinfunction "OUT_1") (pintype "output"))
    )
    (net (code "49") (name "Net-(U12-+IN)") (class "Default")
      (node (ref "C57") (pin "2") (pinfunction "2_2") (pintype "passive"))
      (node (ref "C58") (pin "1") (pinfunction "1_1") (pintype "passive"))
      (node (ref "C62") (pin "2") (pinfunction "2_2") (pintype "passive"))
      (node (ref "L9") (pin "1") (pinfunction "1_1") (pintype "passive"))
      (node (ref "R65") (pin "2") (pinfunction "2_2") (pintype "passive"))
      (node (ref "U12") (pin "3") (pinfunction "+IN_3") (pintype "input"))
    )
    (net (code "50") (name "Net-(U12-OUT)") (class "Default")
      (node (ref "R55") (pin "1") (pinfunction "1_1") (pintype "passive"))
      (node (ref "U12") (pin "1") (pinfunction "OUT_1") (pintype "output"))
    )
    (net (code "51") (name "Net-(U13-+IN)") (class "Default")
      (node (ref "C69") (pin "2") (pinfunction "2_2") (pintype "passive"))
      (node (ref "C70") (pin "1") (pinfunction "1_1") (pintype "passive"))
      (node (ref "C74") (pin "2") (pinfunction "2_2") (pintype "passive"))
      (node (ref "L12") (pin "1") (pinfunction "1_1") (pintype "passive"))
      (node (ref "R66") (pin "2") (pinfunction "2_2") (pintype "passive"))
      (node (ref "U13") (pin "3") (pinfunction "+IN_3") (pintype "input"))
    )
    (net (code "52") (name "Net-(U13-OUT)") (class "Default")
      (node (ref "R56") (pin "1") (pinfunction "1_1") (pintype "passive"))
      (node (ref "U13") (pin "1") (pinfunction "OUT_1") (pintype "output"))
    )
    (net (code "53") (name "unconnected-(C131-Pad1)") (class "Default")
      (node (ref "C131") (pin "1") (pinfunction "1_1") (pintype "passive+no_connect"))
    )
    (net (code "54") (name "unconnected-(C131-Pad2)") (class "Default")
      (node (ref "C131") (pin "2") (pinfunction "2_2") (pintype "passive+no_connect"))
    )
    (net (code "55") (name "unconnected-(C132-Pad1)") (class "Default")
      (node (ref "C132") (pin "1") (pinfunction "1_1") (pintype "passive+no_connect"))
    )
    (net (code "56") (name "unconnected-(C132-Pad2)") (class "Default")
      (node (ref "C132") (pin "2") (pinfunction "2_2") (pintype "passive+no_connect"))
    )
    (net (code "57") (name "unconnected-(C133-Pad1)") (class "Default")
      (node (ref "C133") (pin "1") (pinfunction "1_1") (pintype "passive+no_connect"))
    )
    (net (code "58") (name "unconnected-(C133-Pad2)") (class "Default")
      (node (ref "C133") (pin "2") (pinfunction "2_2") (pintype "passive+no_connect"))
    )
    (net (code "59") (name "unconnected-(C134-Pad1)") (class "Default")
      (node (ref "C134") (pin "1") (pinfunction "1_1") (pintype "passive+no_connect"))
    )
    (net (code "60") (name "unconnected-(C134-Pad2)") (class "Default")
      (node (ref "C134") (pin "2") (pinfunction "2_2") (pintype "passive+no_connect"))
    )
    (net (code "61") (name "unconnected-(U6-NC-Pad6)") (class "Default")
      (node (ref "U6") (pin "6") (pinfunction "NC_6") (pintype "passive+no_connect"))
    )
    (net (code "62") (name "unconnected-(U6-PD-Pad1)") (class "Default")
      (node (ref "U6") (pin "1") (pinfunction "PD_1") (pintype "passive+no_connect"))
    )
    (net (code "63") (name "unconnected-(U7-NC-Pad6)") (class "Default")
      (node (ref "U7") (pin "6") (pinfunction "NC_6") (pintype "passive+no_connect"))
    )
    (net (code "64") (name "unconnected-(U7-PD-Pad1)") (class "Default")
      (node (ref "U7") (pin "1") (pinfunction "PD_1") (pintype "passive+no_connect"))
    )
    (net (code "65") (name "unconnected-(U8-NC-Pad6)") (class "Default")
      (node (ref "U8") (pin "6") (pinfunction "NC_6") (pintype "passive+no_connect"))
    )
    (net (code "66") (name "unconnected-(U8-PD-Pad1)") (class "Default")
      (node (ref "U8") (pin "1") (pinfunction "PD_1") (pintype "passive+no_connect"))
    )
    (net (code "67") (name "unconnected-(U9-NC-Pad6)") (class "Default")
      (node (ref "U9") (pin "6") (pinfunction "NC_6") (pintype "passive+no_connect"))
    )
    (net (code "68") (name "unconnected-(U9-PD-Pad1)") (class "Default")
      (node (ref "U9") (pin "1") (pinfunction "PD_1") (pintype "passive+no_connect"))
    )
  )
)
